# AutoProgramFTDI.net
KiCad netlist of a schematic drawn in EAGLE
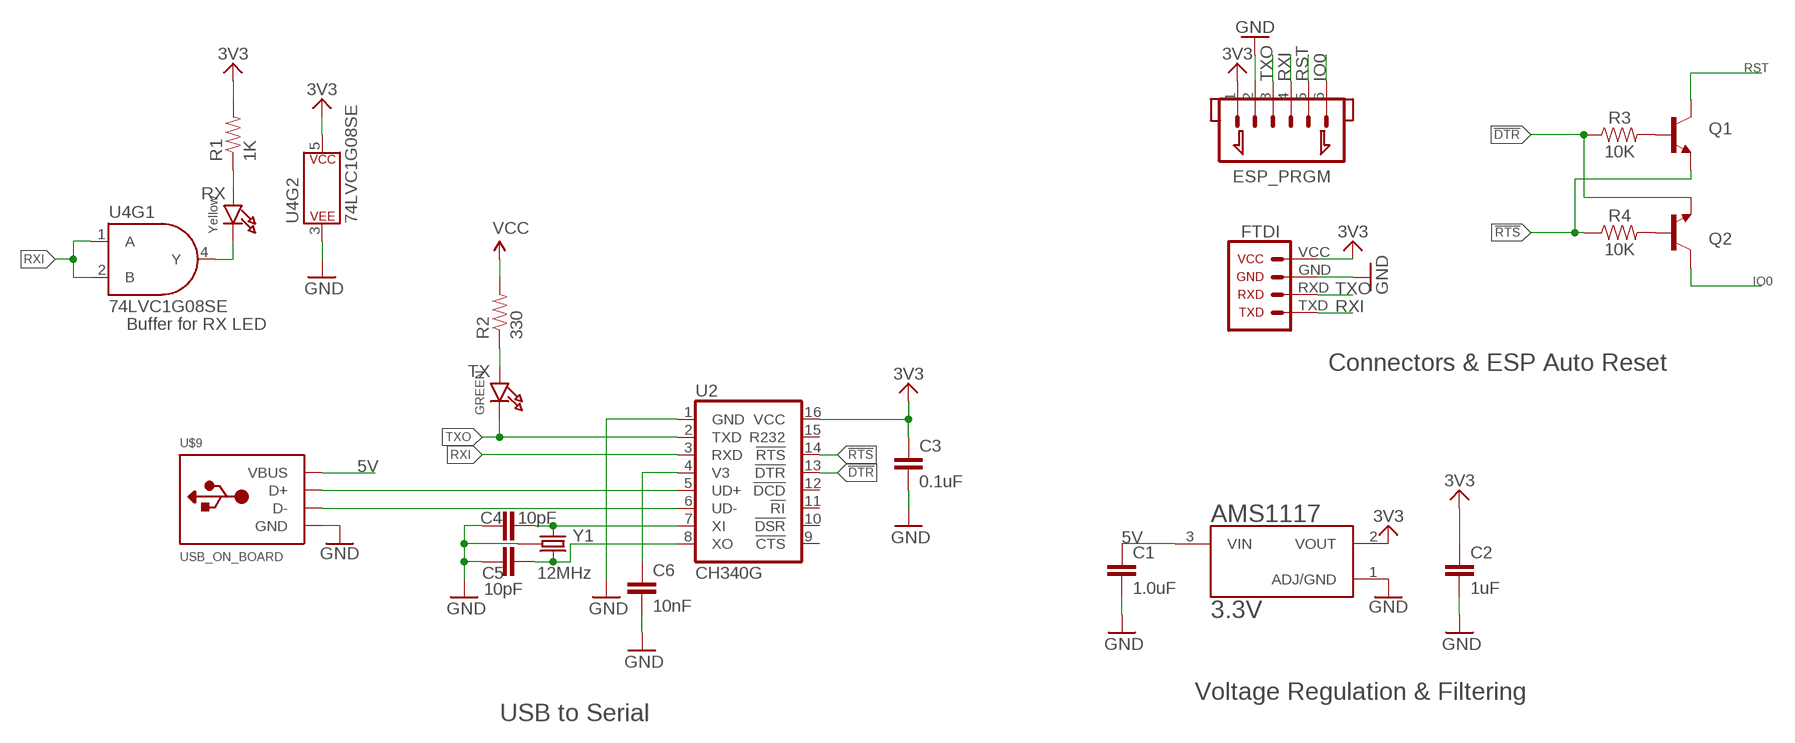
[diagram p0: schematic, sheet 1]

(export (version "E")
  (design (tool "Eeschema 10.0.6"))
  (components
    (comp (ref "AMS1117")
      (value "3.3V")
      (footprint "eagle-import:SOT229P700X180-4N")
      (fields (field (name "MF") "Advanced Monolithic Systems") (field (name "MP") "AMS1117-3.3"))
      (libsource (lib "eagle-import") (part "VREG_AMS1117"))
    )
    (comp (ref "C1")
      (value "1.0uF")
      (footprint "eagle-import:0603-CAP")
      (libsource (lib "eagle-import") (part "1.0UF-16V-10%(0603)"))
    )
    (comp (ref "C2")
      (value "1uF")
      (footprint "eagle-import:0603-CAP")
      (libsource (lib "eagle-import") (part "1.0UF-16V-10%(0603)"))
    )
    (comp (ref "C3")
      (value "0.1uF")
      (footprint "eagle-import:0603-CAP")
      (libsource (lib "eagle-import") (part "0.1UF-25V(+80/-20%)(0603)"))
    )
    (comp (ref "C4")
      (value "10pF")
      (footprint "eagle-import:0603-CAP")
      (libsource (lib "eagle-import") (part "10PF-50V-5%(0603)"))
    )
    (comp (ref "C5")
      (value "10pF")
      (footprint "eagle-import:0603-CAP")
      (libsource (lib "eagle-import") (part "10PF-50V-5%(0603)"))
    )
    (comp (ref "C6")
      (value "10nF")
      (footprint "eagle-import:0603-CAP")
      (libsource (lib "eagle-import") (part "10NF/10000PF-50V-10%(0603)"))
    )
    (comp (ref "ESP_PRGM")
      (value "JST_1.25_6P")
      (footprint "eagle-import:JST1.25_6P")
      (libsource (lib "eagle-import") (part "JST_1.25_6P"))
    )
    (comp (ref "Q1")
      (value "TRANSISTOR_NPNSOT23-3")
      (footprint "eagle-import:SPARKFUN_SOT23-3")
      (libsource (lib "eagle-import") (part "TRANSISTOR_NPNSOT23-3"))
    )
    (comp (ref "Q2")
      (value "TRANSISTOR_NPNSOT23-3")
      (footprint "eagle-import:SPARKFUN_SOT23-3")
      (libsource (lib "eagle-import") (part "TRANSISTOR_NPNSOT23-3"))
    )
    (comp (ref "R1")
      (value "1K")
      (footprint "eagle-import:0603")
      (libsource (lib "eagle-import") (part "RESISTOR0603"))
    )
    (comp (ref "R2")
      (value "330")
      (footprint "eagle-import:0603")
      (libsource (lib "eagle-import") (part "RESISTOR0603"))
    )
    (comp (ref "R3")
      (value "10K")
      (footprint "eagle-import:0603")
      (libsource (lib "eagle-import") (part "RESISTOR0603"))
    )
    (comp (ref "R4")
      (value "10K")
      (footprint "eagle-import:0603")
      (libsource (lib "eagle-import") (part "RESISTOR0603"))
    )
    (comp (ref "RX")
      (value "Yellow")
      (footprint "eagle-import:MICROBUILDER_CHIPLED_0603")
      (libsource (lib "eagle-import") (part "LED0603"))
    )
    (comp (ref "TX")
      (value "GREEN")
      (footprint "eagle-import:MICROBUILDER_CHIPLED_0603")
      (libsource (lib "eagle-import") (part "LED0603"))
    )
    (comp (ref "U$6")
      (value "FTDI")
      (footprint "eagle-import:1X06")
      (libsource (lib "eagle-import") (part "FTDI"))
    )
    (comp (ref "U$9")
      (value "USB_ON_BOARD")
      (footprint "eagle-import:USB_ON_BOARD")
      (libsource (lib "eagle-import") (part "USB_ON_BOARD"))
    )
    (comp (ref "U2")
      (value "CH340G")
      (footprint "eagle-import:SO016")
      (libsource (lib "eagle-import") (part "FTDI_CH340GSMD"))
    )
    (comp (ref "U4")
      (value "74LVC1G08SE")
      (footprint "eagle-import:SOT353")
      (libsource (lib "eagle-import") (part "GATE_7408"))
    )
    (comp (ref "Y1")
      (value "12MHz")
      (footprint "eagle-import:CRYSTAL-SMD-3.2X2.5")
      (libsource (lib "eagle-import") (part "CRYSTAL-GROUNDED3.2X2.5"))
    )
  )
  (nets
    (net (code "1") (name "/5V") (class "Default")
      (node (ref "AMS1117") (pin "3") (pinfunction "VIN_3") (pintype "input"))
      (node (ref "C1") (pin "1") (pinfunction "1_1") (pintype "passive"))
      (node (ref "U$9") (pin "VCC") (pinfunction "VBUS_VCC") (pintype "power_in"))
    )
    (net (code "2") (name "/IO0") (class "Default")
      (node (ref "ESP_PRGM") (pin "6") (pinfunction "6_6") (pintype "passive"))
      (node (ref "Q2") (pin "3") (pinfunction "C_3") (pintype "passive"))
    )
    (net (code "3") (name "/RST") (class "Default")
      (node (ref "ESP_PRGM") (pin "5") (pinfunction "5_5") (pintype "passive"))
      (node (ref "Q1") (pin "3") (pinfunction "C_3") (pintype "passive"))
    )
    (net (code "4") (name "/~{DTR}") (class "Default")
      (node (ref "Q2") (pin "2") (pinfunction "E_2") (pintype "passive"))
      (node (ref "R3") (pin "1") (pinfunction "1_1") (pintype "passive"))
      (node (ref "U2") (pin "13") (pinfunction "~{DTR}_13") (pintype "bidirectional"))
    )
    (net (code "5") (name "/~{RTS}") (class "Default")
      (node (ref "Q1") (pin "2") (pinfunction "E_2") (pintype "passive"))
      (node (ref "R4") (pin "1") (pinfunction "1_1") (pintype "passive"))
      (node (ref "U2") (pin "14") (pinfunction "~{RTS}_14") (pintype "bidirectional"))
    )
    (net (code "6") (name "GND") (class "Default")
      (node (ref "AMS1117") (pin "1") (pinfunction "ADJ/GND_1") (pintype "power_in"))
      (node (ref "C1") (pin "2") (pinfunction "2_2") (pintype "passive"))
      (node (ref "C2") (pin "2") (pinfunction "2_2") (pintype "passive"))
      (node (ref "C3") (pin "2") (pinfunction "2_2") (pintype "passive"))
      (node (ref "C4") (pin "1") (pinfunction "1_1") (pintype "passive"))
      (node (ref "C5") (pin "1") (pinfunction "1_1") (pintype "passive"))
      (node (ref "C6") (pin "2") (pinfunction "2_2") (pintype "passive"))
      (node (ref "ESP_PRGM") (pin "2") (pinfunction "2_2") (pintype "passive"))
      (node (ref "U$6") (pin "GND") (pinfunction "GND_GND") (pintype "passive"))
      (node (ref "U$9") (pin "GND") (pinfunction "GND_GND") (pintype "power_in"))
      (node (ref "U2") (pin "1") (pinfunction "GND_1") (pintype "bidirectional"))
      (node (ref "U4") (pin "3") (pinfunction "P$V-_3") (pintype "bidirectional"))
      (node (ref "Y1") (pin "2") (pinfunction "GND_2") (pintype "passive"))
      (node (ref "Y1") (pin "4") (pinfunction "GND_4") (pintype "passive"))
    )
    (net (code "7") (name "Net-(Q1-B)") (class "Default")
      (node (ref "Q1") (pin "1") (pinfunction "B_1") (pintype "passive"))
      (node (ref "R3") (pin "2") (pinfunction "2_2") (pintype "passive"))
    )
    (net (code "8") (name "Net-(Q2-B)") (class "Default")
      (node (ref "Q2") (pin "1") (pinfunction "B_1") (pintype "passive"))
      (node (ref "R4") (pin "2") (pinfunction "2_2") (pintype "passive"))
    )
    (net (code "9") (name "Net-(R1-Pad1)") (class "Default")
      (node (ref "R1") (pin "1") (pinfunction "1_1") (pintype "passive"))
      (node (ref "RX") (pin "A") (pinfunction "A_A") (pintype "passive"))
    )
    (net (code "10") (name "Net-(R2-Pad1)") (class "Default")
      (node (ref "R2") (pin "1") (pinfunction "1_1") (pintype "passive"))
      (node (ref "TX") (pin "A") (pinfunction "A_A") (pintype "passive"))
    )
    (net (code "11") (name "Net-(U2-UD+)") (class "Default")
      (node (ref "U$9") (pin "D+") (pinfunction "D+_D+") (pintype "bidirectional"))
      (node (ref "U2") (pin "5") (pinfunction "UD+_5") (pintype "bidirectional"))
    )
    (net (code "12") (name "Net-(U2-UD-)") (class "Default")
      (node (ref "U$9") (pin "D-") (pinfunction "D-_D-") (pintype "bidirectional"))
      (node (ref "U2") (pin "6") (pinfunction "UD-_6") (pintype "bidirectional"))
    )
    (net (code "13") (name "Net-(U2-V3)") (class "Default")
      (node (ref "C6") (pin "1") (pinfunction "1_1") (pintype "passive"))
      (node (ref "U2") (pin "4") (pinfunction "V3_4") (pintype "bidirectional"))
    )
    (net (code "14") (name "Net-(U2-XI)") (class "Default")
      (node (ref "C4") (pin "2") (pinfunction "2_2") (pintype "passive"))
      (node (ref "U2") (pin "7") (pinfunction "XI_7") (pintype "bidirectional"))
      (node (ref "Y1") (pin "1") (pinfunction "1_1") (pintype "passive"))
    )
    (net (code "15") (name "Net-(U2-XO)") (class "Default")
      (node (ref "C5") (pin "2") (pinfunction "2_2") (pintype "passive"))
      (node (ref "U2") (pin "8") (pinfunction "XO_8") (pintype "bidirectional"))
      (node (ref "Y1") (pin "3") (pinfunction "2_3") (pintype "passive"))
    )
    (net (code "16") (name "Net-(U4A-Y)") (class "Default")
      (node (ref "RX") (pin "C") (pinfunction "C_C") (pintype "passive"))
      (node (ref "U4") (pin "4") (pinfunction "Y_4") (pintype "bidirectional"))
    )
    (net (code "17") (name "RXI") (class "Default")
      (node (ref "ESP_PRGM") (pin "4") (pinfunction "4_4") (pintype "passive"))
      (node (ref "U$6") (pin "TXD") (pinfunction "TXD_TXD") (pintype "passive"))
      (node (ref "U2") (pin "3") (pinfunction "RXD_3") (pintype "bidirectional"))
      (node (ref "U4") (pin "1") (pinfunction "A_1") (pintype "bidirectional"))
      (node (ref "U4") (pin "2") (pinfunction "B_2") (pintype "bidirectional"))
    )
    (net (code "18") (name "SUPPLY_3.3V") (class "Default")
      (node (ref "AMS1117") (pin "2") (pinfunction "VOUT_2") (pintype "output"))
      (node (ref "C2") (pin "1") (pinfunction "1_1") (pintype "passive"))
      (node (ref "C3") (pin "1") (pinfunction "1_1") (pintype "passive"))
      (node (ref "ESP_PRGM") (pin "1") (pinfunction "1_1") (pintype "passive"))
      (node (ref "R1") (pin "2") (pinfunction "2_2") (pintype "passive"))
      (node (ref "U$6") (pin "VCC") (pinfunction "VCC_VCC") (pintype "passive"))
      (node (ref "U2") (pin "16") (pinfunction "VCC_16") (pintype "bidirectional"))
      (node (ref "U4") (pin "5") (pinfunction "P$V+_5") (pintype "bidirectional"))
    )
    (net (code "19") (name "TXO") (class "Default")
      (node (ref "ESP_PRGM") (pin "3") (pinfunction "3_3") (pintype "passive"))
      (node (ref "TX") (pin "C") (pinfunction "C_C") (pintype "passive"))
      (node (ref "U$6") (pin "RXD") (pinfunction "RXD_RXD") (pintype "passive"))
      (node (ref "U2") (pin "2") (pinfunction "TXD_2") (pintype "bidirectional"))
    )
    (net (code "20") (name "VCC") (class "Default")
      (node (ref "R2") (pin "2") (pinfunction "2_2") (pintype "passive"))
    )
    (net (code "21") (name "unconnected-(U2-R232-Pad15)") (class "Default")
      (node (ref "U2") (pin "15") (pinfunction "R232_15") (pintype "bidirectional"))
    )
    (net (code "22") (name "unconnected-(U2-~{CTS}-Pad9)") (class "Default")
      (node (ref "U2") (pin "9") (pinfunction "~{CTS}_9") (pintype "bidirectional"))
    )
    (net (code "23") (name "unconnected-(U2-~{DCD}-Pad12)") (class "Default")
      (node (ref "U2") (pin "12") (pinfunction "~{DCD}_12") (pintype "bidirectional"))
    )
    (net (code "24") (name "unconnected-(U2-~{DSR}-Pad10)") (class "Default")
      (node (ref "U2") (pin "10") (pinfunction "~{DSR}_10") (pintype "bidirectional"))
    )
    (net (code "25") (name "unconnected-(U2-~{RI}-Pad11)") (class "Default")
      (node (ref "U2") (pin "11") (pinfunction "~{RI}_11") (pintype "bidirectional"))
    )
  )
)
